# ESP32_WiFi.net
KiCad netlist of a schematic drawn in Altium Designer
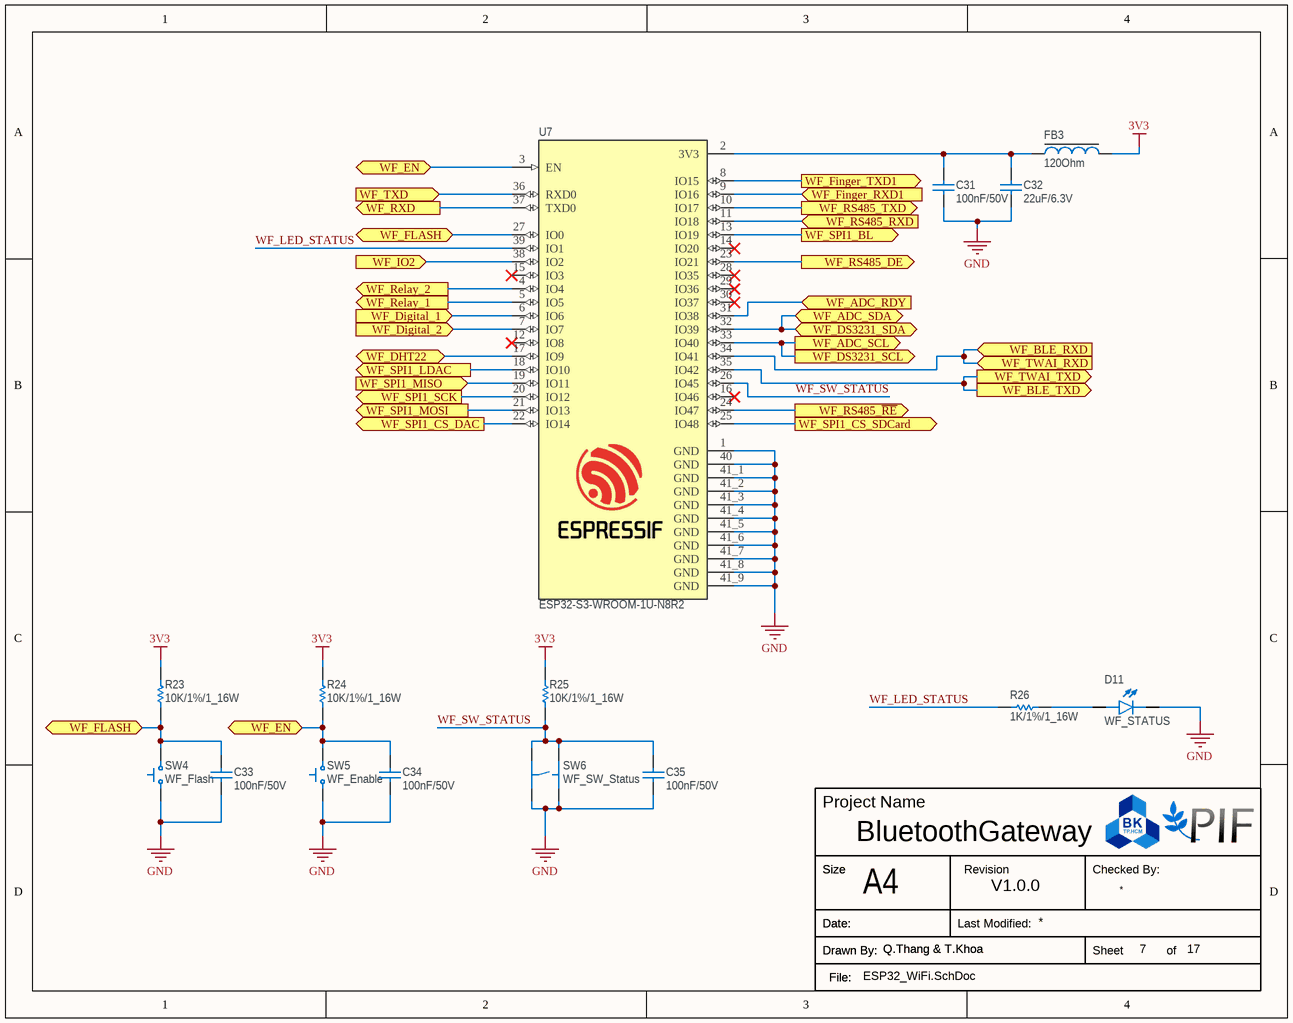
[diagram p0: ESP32_WiFi.SchDoc]

(export (version "E")
  (design (tool "Eeschema 10.0.6"))
  (components
    (comp (ref "C31")
      (value "100nF/50V")
      (footprint "CAP_0805")
      (description "CAP, size 0805, 100nF, 50V")
      (fields (field (name "SUPPLY PART NUMBER") "Tụ Gốm 0805 100nF (0.1uF) 50V"))
      (libsource (lib "BluetoothTracking") (part "Ceramic_Cap_100nF_50V_0805"))
    )
    (comp (ref "C32")
      (value "22uF/6.3V")
      (footprint "CAP_0805")
      (description "CAP, size 0805, 22uF, 6.3V")
      (fields (field (name "SUPPLY PART NUMBER") "Tụ Gốm 0805 22uF 6.3V"))
      (libsource (lib "BluetoothTracking") (part "Ceramic_Cap_22uF_6.3V_0805"))
    )
    (comp (ref "C33")
      (value "100nF/50V")
      (footprint "CAP_0402")
      (description "CAP, size 0402, 100nF, 50V")
      (fields (field (name "SUPPLY PART NUMBER") "Tụ Gốm 0402 100nF (0.1uF) 50V"))
      (libsource (lib "BluetoothTracking") (part "Ceramic_Cap_100nF_50V_0402"))
    )
    (comp (ref "C34")
      (value "100nF/50V")
      (footprint "CAP_0402")
      (description "CAP, size 0402, 100nF, 50V")
      (fields (field (name "SUPPLY PART NUMBER") "Tụ Gốm 0402 100nF (0.1uF) 50V"))
      (libsource (lib "BluetoothTracking") (part "Ceramic_Cap_100nF_50V_0402"))
    )
    (comp (ref "C35")
      (value "100nF/50V")
      (footprint "CAP_0402")
      (description "CAP, size 0402, 100nF, 50V")
      (fields (field (name "SUPPLY PART NUMBER") "Tụ Gốm 0402 100nF (0.1uF) 50V"))
      (libsource (lib "BluetoothTracking") (part "Ceramic_Cap_100nF_50V_0402"))
    )
    (comp (ref "D11")
      (value "WF_STATUS")
      (footprint "LED_0603Y")
      (description "LED Yellow 0603")
      (fields (field (name "SUPPLY PART NUMBER") "LED Vàng 0603 Dán SMD Trong Suốt Harvatek"))
      (libsource (lib "BluetoothTracking") (part "LED_Yellow_0603"))
    )
    (comp (ref "FB3")
      (value "120Ohm")
      (footprint "Ferrite_Bead_0805")
      (description "Ferrite Bead, size 0805, 120Ohm, 2A")
      (fields (field (name "SUPPLY PART NUMBER") "CBW201209U121T Ferrite Beads 2A 120 Ohm 0805"))
      (libsource (lib "BluetoothTracking") (part "Ferrite_Bead_120Ohm_2A_0805"))
    )
    (comp (ref "R23")
      (value "10K/1%/1_16W")
      (footprint "RESISTOR_0402")
      (description "Resistor 0402 10KOhm 1% 1_16W")
      (fields (field (name "SUPPLY PART NUMBER") "Điện Trở 10 KOhm 0402 1%"))
      (libsource (lib "BluetoothTracking") (part "Res_10K_0402_1%"))
    )
    (comp (ref "R24")
      (value "10K/1%/1_16W")
      (footprint "RESISTOR_0402")
      (description "Resistor 0402 10KOhm 1% 1_16W")
      (fields (field (name "SUPPLY PART NUMBER") "Điện Trở 10 KOhm 0402 1%"))
      (libsource (lib "BluetoothTracking") (part "Res_10K_0402_1%"))
    )
    (comp (ref "R25")
      (value "10K/1%/1_16W")
      (footprint "RESISTOR_0402")
      (description "Resistor 0402 10KOhm 1% 1_16W")
      (fields (field (name "SUPPLY PART NUMBER") "Điện Trở 10 KOhm 0402 1%"))
      (libsource (lib "BluetoothTracking") (part "Res_10K_0402_1%"))
    )
    (comp (ref "R26")
      (value "1K/1%/1_16W")
      (footprint "RESISTOR_0402")
      (description "Resistor 0402 1KOhm 1% 1_16W")
      (fields (field (name "SUPPLY PART NUMBER") "Điện Trở 1 KOhm 0402 1%"))
      (libsource (lib "BluetoothTracking") (part "Res_1K_0402_1%"))
    )
    (comp (ref "SW4")
      (value "WF_Flash")
      (footprint "Button_3x4mm_SMD_2P")
      (fields (field (name "SUPPLY PART NUMBER") "Nút Nhấn 3x4mm Cao 2.5mm 2 Chân SMD"))
      (libsource (lib "BluetoothTracking") (part "Button_SMD_3x4mm_2P"))
    )
    (comp (ref "SW5")
      (value "WF_Enable")
      (footprint "Button_3x4mm_SMD_2P")
      (fields (field (name "SUPPLY PART NUMBER") "Nút Nhấn 3x4mm Cao 2.5mm 2 Chân SMD"))
      (libsource (lib "BluetoothTracking") (part "Button_SMD_3x4mm_2P"))
    )
    (comp (ref "SW6")
      (value "WF_SW_Status")
      (footprint "Button_4.5x4.7mm_SMD_4P")
      (fields (field (name "SUPPLY PART NUMBER") "Nút Nhấn Rùa 4.5x4.7mm Cao 1.65mm 4 Chân SMD"))
      (libsource (lib "BluetoothTracking") (part "Button_SMD_4.5x4.7mm_4P"))
    )
    (comp (ref "U7")
      (value "ESP32-S3-WROOM-1U-N8R2")
      (footprint "XCVR_ESP32-S3-WROOM-1U-N16R8")
      (fields
        (field (name "SUPPLY PART NUMBER") "ESP32-S3-WROOM-1U-N8R2 Module WiFi Bluetooth 8MB Flash, 2MB SRAM 2.4GHz")
      )
      (libsource (lib "BluetoothTracking") (part "ESP32-S3-WROOM-1U-N8R2"))
    )
  )
  (nets
    (net (code "1") (name "/WF_ADC_RDY") (class "Default")
      (node (ref "U7") (pin "31") (pinfunction "IO38_31") (pintype "bidirectional"))
    )
    (net (code "2") (name "/WF_ADC_SCL") (class "Default")
      (node (ref "U7") (pin "33") (pinfunction "IO40_33") (pintype "bidirectional"))
    )
    (net (code "3") (name "/WF_ADC_SDA") (class "Default")
      (node (ref "U7") (pin "32") (pinfunction "IO39_32") (pintype "bidirectional"))
    )
    (net (code "4") (name "/WF_BLE_RXD") (class "Default")
      (node (ref "U7") (pin "34") (pinfunction "IO41_34") (pintype "bidirectional"))
    )
    (net (code "5") (name "/WF_BLE_TXD") (class "Default")
      (node (ref "U7") (pin "35") (pinfunction "IO42_35") (pintype "bidirectional"))
    )
    (net (code "6") (name "/WF_DHT22") (class "Default")
      (node (ref "U7") (pin "17") (pinfunction "IO9_17") (pintype "bidirectional"))
    )
    (net (code "7") (name "/WF_Digital_1") (class "Default")
      (node (ref "U7") (pin "6") (pinfunction "IO6_6") (pintype "bidirectional"))
    )
    (net (code "8") (name "/WF_Digital_2") (class "Default")
      (node (ref "U7") (pin "7") (pinfunction "IO7_7") (pintype "bidirectional"))
    )
    (net (code "9") (name "/WF_EN") (class "Default")
      (node (ref "C34") (pin "2") (pinfunction "2_2") (pintype "passive"))
      (node (ref "R24") (pin "1") (pinfunction "1_1") (pintype "passive"))
      (node (ref "SW5") (pin "2") (pinfunction "2_2") (pintype "passive"))
      (node (ref "U7") (pin "3") (pinfunction "EN_3") (pintype "input"))
    )
    (net (code "10") (name "/WF_FLASH") (class "Default")
      (node (ref "C33") (pin "2") (pinfunction "2_2") (pintype "passive"))
      (node (ref "R23") (pin "1") (pinfunction "1_1") (pintype "passive"))
      (node (ref "SW4") (pin "2") (pinfunction "2_2") (pintype "passive"))
      (node (ref "U7") (pin "27") (pinfunction "IO0_27") (pintype "bidirectional"))
    )
    (net (code "11") (name "/WF_Finger_RXD1") (class "Default")
      (node (ref "U7") (pin "9") (pinfunction "IO16_9") (pintype "bidirectional"))
    )
    (net (code "12") (name "/WF_Finger_TXD1") (class "Default")
      (node (ref "U7") (pin "8") (pinfunction "IO15_8") (pintype "bidirectional"))
    )
    (net (code "13") (name "/WF_IO2") (class "Default")
      (node (ref "U7") (pin "38") (pinfunction "IO2_38") (pintype "bidirectional"))
    )
    (net (code "14") (name "/WF_LED_STATUS") (class "Default")
      (node (ref "R26") (pin "1") (pinfunction "1_1") (pintype "passive"))
      (node (ref "U7") (pin "39") (pinfunction "IO1_39") (pintype "bidirectional"))
    )
    (net (code "15") (name "/WF_RS485_DE") (class "Default")
      (node (ref "U7") (pin "23") (pinfunction "IO21_23") (pintype "bidirectional"))
    )
    (net (code "16") (name "/WF_RS485_RXD") (class "Default")
      (node (ref "U7") (pin "11") (pinfunction "IO18_11") (pintype "bidirectional"))
    )
    (net (code "17") (name "/WF_RS485_TXD") (class "Default")
      (node (ref "U7") (pin "10") (pinfunction "IO17_10") (pintype "bidirectional"))
    )
    (net (code "18") (name "/WF_RS485_~{RE}") (class "Default")
      (node (ref "U7") (pin "24") (pinfunction "IO47_24") (pintype "bidirectional"))
    )
    (net (code "19") (name "/WF_RXD") (class "Default")
      (node (ref "U7") (pin "37") (pinfunction "TXD0_37") (pintype "bidirectional"))
    )
    (net (code "20") (name "/WF_Relay_1") (class "Default")
      (node (ref "U7") (pin "5") (pinfunction "IO5_5") (pintype "bidirectional"))
    )
    (net (code "21") (name "/WF_Relay_2") (class "Default")
      (node (ref "U7") (pin "4") (pinfunction "IO4_4") (pintype "bidirectional"))
    )
    (net (code "22") (name "/WF_SPI1_BL") (class "Default")
      (node (ref "U7") (pin "13") (pinfunction "IO19_13") (pintype "bidirectional"))
    )
    (net (code "23") (name "/WF_SPI1_CS_DAC") (class "Default")
      (node (ref "U7") (pin "22") (pinfunction "IO14_22") (pintype "bidirectional"))
    )
    (net (code "24") (name "/WF_SPI1_CS_SDCard") (class "Default")
      (node (ref "U7") (pin "25") (pinfunction "IO48_25") (pintype "bidirectional"))
    )
    (net (code "25") (name "/WF_SPI1_LDAC") (class "Default")
      (node (ref "U7") (pin "18") (pinfunction "IO10_18") (pintype "bidirectional"))
    )
    (net (code "26") (name "/WF_SPI1_MISO") (class "Default")
      (node (ref "U7") (pin "19") (pinfunction "IO11_19") (pintype "bidirectional"))
    )
    (net (code "27") (name "/WF_SPI1_MOSI") (class "Default")
      (node (ref "U7") (pin "21") (pinfunction "IO13_21") (pintype "bidirectional"))
    )
    (net (code "28") (name "/WF_SPI1_SCK") (class "Default")
      (node (ref "U7") (pin "20") (pinfunction "IO12_20") (pintype "bidirectional"))
    )
    (net (code "29") (name "/WF_SW_STATUS") (class "Default")
      (node (ref "C35") (pin "2") (pinfunction "2_2") (pintype "passive"))
      (node (ref "R25") (pin "1") (pinfunction "1_1") (pintype "passive"))
      (node (ref "SW6") (pin "2") (pinfunction "2_2") (pintype "passive"))
      (node (ref "SW6") (pin "4") (pinfunction "4_4") (pintype "passive"))
      (node (ref "U7") (pin "26") (pinfunction "IO45_26") (pintype "bidirectional"))
    )
    (net (code "30") (name "/WF_TXD") (class "Default")
      (node (ref "U7") (pin "36") (pinfunction "RXD0_36") (pintype "bidirectional"))
    )
    (net (code "31") (name "3V3") (class "Default")
      (node (ref "FB3") (pin "2") (pinfunction "2_2") (pintype "passive"))
      (node (ref "R23") (pin "2") (pinfunction "2_2") (pintype "passive"))
      (node (ref "R24") (pin "2") (pinfunction "2_2") (pintype "passive"))
      (node (ref "R25") (pin "2") (pinfunction "2_2") (pintype "passive"))
    )
    (net (code "32") (name "GND") (class "Default")
      (node (ref "C31") (pin "1") (pinfunction "1_1") (pintype "passive"))
      (node (ref "C32") (pin "1") (pinfunction "1_1") (pintype "passive"))
      (node (ref "C33") (pin "1") (pinfunction "1_1") (pintype "passive"))
      (node (ref "C34") (pin "1") (pinfunction "1_1") (pintype "passive"))
      (node (ref "C35") (pin "1") (pinfunction "1_1") (pintype "passive"))
      (node (ref "D11") (pin "C") (pinfunction "C_C") (pintype "passive"))
      (node (ref "SW4") (pin "1") (pinfunction "1_1") (pintype "passive"))
      (node (ref "SW5") (pin "1") (pinfunction "1_1") (pintype "passive"))
      (node (ref "SW6") (pin "1") (pinfunction "1_1") (pintype "passive"))
      (node (ref "SW6") (pin "3") (pinfunction "3_3") (pintype "passive"))
      (node (ref "U7") (pin "1") (pinfunction "GND_1") (pintype "power_in"))
      (node (ref "U7") (pin "40") (pinfunction "GND_40") (pintype "power_in"))
      (node (ref "U7") (pin "41_1") (pinfunction "GND_41_1") (pintype "power_in"))
      (node (ref "U7") (pin "41_2") (pinfunction "GND_41_2") (pintype "power_in"))
      (node (ref "U7") (pin "41_3") (pinfunction "GND_41_3") (pintype "power_in"))
      (node (ref "U7") (pin "41_4") (pinfunction "GND_41_4") (pintype "power_in"))
      (node (ref "U7") (pin "41_5") (pinfunction "GND_41_5") (pintype "power_in"))
      (node (ref "U7") (pin "41_6") (pinfunction "GND_41_6") (pintype "power_in"))
      (node (ref "U7") (pin "41_7") (pinfunction "GND_41_7") (pintype "power_in"))
      (node (ref "U7") (pin "41_8") (pinfunction "GND_41_8") (pintype "power_in"))
      (node (ref "U7") (pin "41_9") (pinfunction "GND_41_9") (pintype "power_in"))
    )
    (net (code "33") (name "Net-(D11-PadA)") (class "Default")
      (node (ref "D11") (pin "A") (pinfunction "A_A") (pintype "passive"))
      (node (ref "R26") (pin "2") (pinfunction "2_2") (pintype "passive"))
    )
    (net (code "34") (name "Net-(U7-3V3)") (class "Default")
      (node (ref "C31") (pin "2") (pinfunction "2_2") (pintype "passive"))
      (node (ref "C32") (pin "2") (pinfunction "2_2") (pintype "passive"))
      (node (ref "FB3") (pin "1") (pinfunction "1_1") (pintype "passive"))
      (node (ref "U7") (pin "2") (pinfunction "3V3_2") (pintype "power_in"))
    )
    (net (code "35") (name "unconnected-(U7-IO3-Pad15)") (class "Default")
      (node (ref "U7") (pin "15") (pinfunction "IO3_15") (pintype "bidirectional+no_connect"))
    )
    (net (code "36") (name "unconnected-(U7-IO8-Pad12)") (class "Default")
      (node (ref "U7") (pin "12") (pinfunction "IO8_12") (pintype "bidirectional+no_connect"))
    )
    (net (code "37") (name "unconnected-(U7-IO20-Pad14)") (class "Default")
      (node (ref "U7") (pin "14") (pinfunction "IO20_14") (pintype "bidirectional+no_connect"))
    )
    (net (code "38") (name "unconnected-(U7-IO35-Pad28)") (class "Default")
      (node (ref "U7") (pin "28") (pinfunction "IO35_28") (pintype "bidirectional+no_connect"))
    )
    (net (code "39") (name "unconnected-(U7-IO36-Pad29)") (class "Default")
      (node (ref "U7") (pin "29") (pinfunction "IO36_29") (pintype "bidirectional+no_connect"))
    )
    (net (code "40") (name "unconnected-(U7-IO37-Pad30)") (class "Default")
      (node (ref "U7") (pin "30") (pinfunction "IO37_30") (pintype "bidirectional+no_connect"))
    )
    (net (code "41") (name "unconnected-(U7-IO46-Pad16)") (class "Default")
      (node (ref "U7") (pin "16") (pinfunction "IO46_16") (pintype "bidirectional+no_connect"))
    )
  )
)
